# MCU_B.net
KiCad netlist of a schematic drawn in Altium Designer
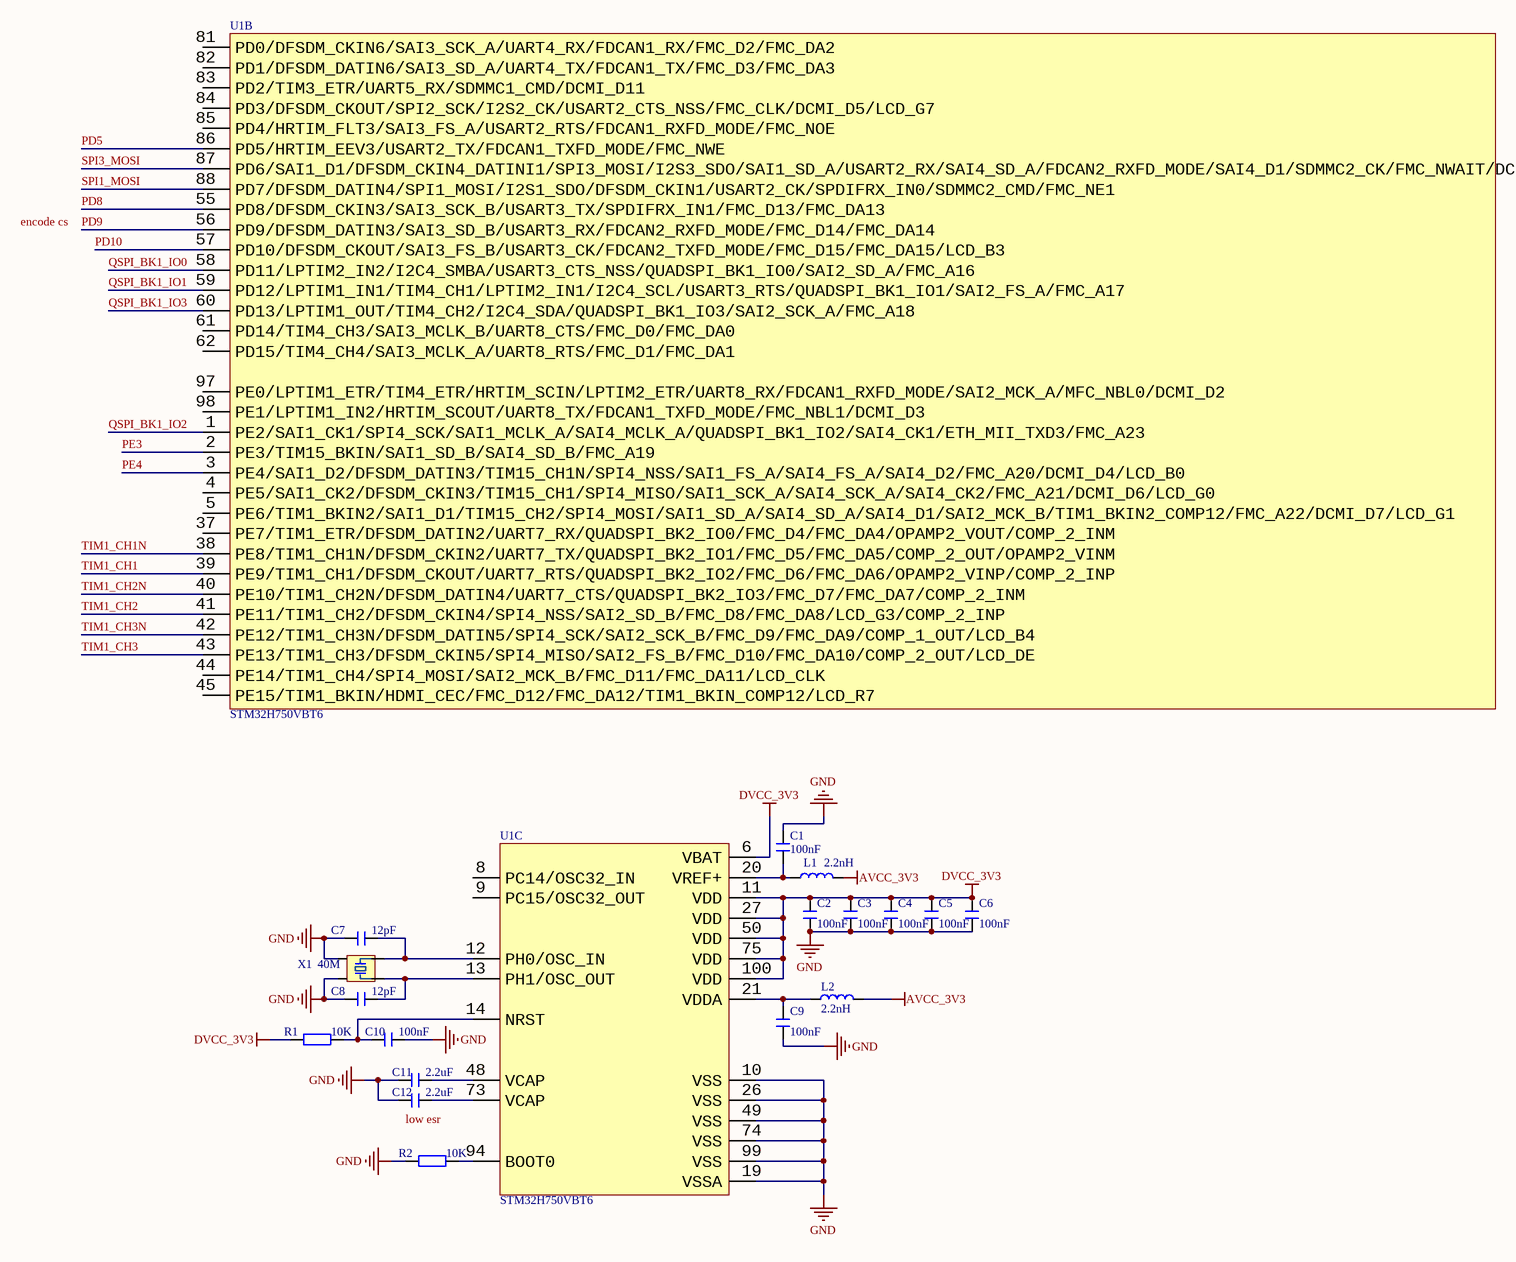
[diagram p0: MCU_B.SchDoc]

(export (version "E")
  (design (tool "Eeschema 10.0.6"))
  (components
    (comp (ref "C1")
      (value "100nF")
      (footprint "C 0402_L")
      (description "无极性贴片电容")
      (fields (field (name "版权归属") "源创客"))
      (libsource (lib "3.1   - 电阻-电容-电感") (part "C"))
    )
    (comp (ref "C2")
      (value "100nF")
      (footprint "C 0402_L")
      (description "无极性贴片电容")
      (fields (field (name "版权归属") "源创客"))
      (libsource (lib "3.1   - 电阻-电容-电感") (part "C"))
    )
    (comp (ref "C3")
      (value "100nF")
      (footprint "C 0402_L")
      (description "无极性贴片电容")
      (fields (field (name "版权归属") "源创客"))
      (libsource (lib "3.1   - 电阻-电容-电感") (part "C"))
    )
    (comp (ref "C4")
      (value "100nF")
      (footprint "C 0402_L")
      (description "无极性贴片电容")
      (fields (field (name "版权归属") "源创客"))
      (libsource (lib "3.1   - 电阻-电容-电感") (part "C"))
    )
    (comp (ref "C5")
      (value "100nF")
      (footprint "C 0402_L")
      (description "无极性贴片电容")
      (fields (field (name "版权归属") "源创客"))
      (libsource (lib "3.1   - 电阻-电容-电感") (part "C"))
    )
    (comp (ref "C6")
      (value "100nF")
      (footprint "C 0402_L")
      (description "无极性贴片电容")
      (fields (field (name "版权归属") "源创客"))
      (libsource (lib "3.1   - 电阻-电容-电感") (part "C"))
    )
    (comp (ref "C7")
      (value "12pF")
      (footprint "C 0402_L")
      (description "无极性贴片电容")
      (fields (field (name "版权归属") "源创客"))
      (libsource (lib "3.1   - 电阻-电容-电感") (part "C"))
    )
    (comp (ref "C8")
      (value "12pF")
      (footprint "C 0402_L")
      (description "无极性贴片电容")
      (fields (field (name "版权归属") "源创客"))
      (libsource (lib "3.1   - 电阻-电容-电感") (part "C"))
    )
    (comp (ref "C9")
      (value "100nF")
      (footprint "C 0402_L")
      (description "无极性贴片电容")
      (fields (field (name "版权归属") "源创客"))
      (libsource (lib "3.1   - 电阻-电容-电感") (part "C"))
    )
    (comp (ref "C10")
      (value "100nF")
      (footprint "C 0402_L")
      (description "无极性贴片电容")
      (fields (field (name "版权归属") "源创客"))
      (libsource (lib "3.1   - 电阻-电容-电感") (part "C"))
    )
    (comp (ref "C11")
      (value "2.2uF")
      (footprint "C 0402_L")
      (description "无极性贴片电容")
      (fields (field (name "版权归属") "源创客"))
      (libsource (lib "3.1   - 电阻-电容-电感") (part "C"))
    )
    (comp (ref "C12")
      (value "2.2uF")
      (footprint "C 0402_L")
      (description "无极性贴片电容")
      (fields (field (name "版权归属") "源创客"))
      (libsource (lib "3.1   - 电阻-电容-电感") (part "C"))
    )
    (comp (ref "L1")
      (value "2.2nH")
      (footprint "L 0402")
      (description "小功率贴片电感")
      (fields (field (name "版权归属") "源创客"))
      (libsource (lib "3.1   - 电阻-电容-电感") (part "L"))
    )
    (comp (ref "L2")
      (value "2.2nH")
      (footprint "L 0402")
      (description "小功率贴片电感")
      (fields (field (name "版权归属") "源创客"))
      (libsource (lib "3.1   - 电阻-电容-电感") (part "L"))
    )
    (comp (ref "R1")
      (value "10K")
      (footprint "R 0402_L")
      (description "贴片电阻")
      (fields (field (name "版权归属") "源创客"))
      (libsource (lib "3.1   - 电阻-电容-电感") (part "R"))
    )
    (comp (ref "R2")
      (value "10K")
      (footprint "R 0402_L")
      (description "贴片电阻")
      (fields (field (name "版权归属") "源创客"))
      (libsource (lib "3.1   - 电阻-电容-电感") (part "R"))
    )
    (comp (ref "U1")
      (value "STM32H750VBT6")
      (footprint "LQFP100 14x14_L")
      (libsource (lib "STM32芯片") (part "STM32H750VBT6"))
    )
    (comp (ref "X1")
      (value "40M")
      (footprint "OSC 2016-4P")
      (description "4脚无源晶振")
      (fields (field (name "版权归属") "源创客"))
      (libsource (lib "10.1 - 保险丝-晶振") (part "XTAL-4P"))
    )
  )
  (nets
    (net (code "1") (name "/PD5") (class "Default")
      (node (ref "U1") (pin "86") (pinfunction "PD5/HRTIM_EEV3/USART2_TX/FDCAN1_TXFD_MODE/FMC_NWE_86") (pintype "passive"))
    )
    (net (code "2") (name "/PD8") (class "Default")
      (node (ref "U1") (pin "55") (pinfunction "PD8/DFSDM_CKIN3/SAI3_SCK_B/USART3_TX/SPDIFRX_IN1/FMC_D13/FMC_DA13_55") (pintype "passive"))
    )
    (net (code "3") (name "/PD9") (class "Default")
      (node (ref "U1") (pin "56") (pinfunction "PD9/DFSDM_DATIN3/SAI3_SD_B/USART3_RX/FDCAN2_RXFD_MODE/FMC_D14/FMC_DA14_56") (pintype "passive"))
    )
    (net (code "4") (name "/PD10") (class "Default")
      (node (ref "U1") (pin "57") (pinfunction "PD10/DFSDM_CKOUT/SAI3_FS_B/USART3_CK/FDCAN2_TXFD_MODE/FMC_D15/FMC_DA15/LCD_B3_57") (pintype "passive"))
    )
    (net (code "5") (name "/PE3") (class "Default")
      (node (ref "U1") (pin "2") (pinfunction "PE3/TIM15_BKIN/SAI1_SD_B/SAI4_SD_B/FMC_A19_2") (pintype "passive"))
    )
    (net (code "6") (name "/PE4") (class "Default")
      (node (ref "U1") (pin "3") (pinfunction "PE4/SAI1_D2/DFSDM_DATIN3/TIM15_CH1N/SPI4_NSS/SAI1_FS_A/SAI4_FS_A/SAI4_D2/FMC_A20/DCMI_D4/LCD_B0_3") (pintype "passive"))
    )
    (net (code "7") (name "/QSPI_BK1_IO0") (class "Default")
      (node (ref "U1") (pin "58") (pinfunction "PD11/LPTIM2_IN2/I2C4_SMBA/USART3_CTS_NSS/QUADSPI_BK1_IO0/SAI2_SD_A/FMC_A16_58") (pintype "passive"))
    )
    (net (code "8") (name "/QSPI_BK1_IO1") (class "Default")
      (node (ref "U1") (pin "59") (pinfunction "PD12/LPTIM1_IN1/TIM4_CH1/LPTIM2_IN1/I2C4_SCL/USART3_RTS/QUADSPI_BK1_IO1/SAI2_FS_A/FMC_A17_59") (pintype "passive"))
    )
    (net (code "9") (name "/QSPI_BK1_IO2") (class "Default")
      (node (ref "U1") (pin "1") (pinfunction "PE2/SAI1_CK1/SPI4_SCK/SAI1_MCLK_A/SAI4_MCLK_A/QUADSPI_BK1_IO2/SAI4_CK1/ETH_MII_TXD3/FMC_A23_1") (pintype "passive"))
    )
    (net (code "10") (name "/QSPI_BK1_IO3") (class "Default")
      (node (ref "U1") (pin "60") (pinfunction "PD13/LPTIM1_OUT/TIM4_CH2/I2C4_SDA/QUADSPI_BK1_IO3/SAI2_SCK_A/FMC_A18_60") (pintype "passive"))
    )
    (net (code "11") (name "/SPI1_MOSI") (class "Default")
      (node (ref "U1") (pin "88") (pinfunction "PD7/DFSDM_DATIN4/SPI1_MOSI/I2S1_SDO/DFSDM_CKIN1/USART2_CK/SPDIFRX_IN0/SDMMC2_CMD/FMC_NE1_88") (pintype "passive"))
    )
    (net (code "12") (name "/SPI3_MOSI") (class "Default")
      (node (ref "U1") (pin "87") (pinfunction "PD6/SAI1_D1/DFSDM_CKIN4_DATINI1/SPI3_MOSI/I2S3_SDO/SAI1_SD_A/USART2_RX/SAI4_SD_A/FDCAN2_RXFD_MODE/SAI4_D1/SDMMC2_CK/FMC_NWAIT/DCMI_D10/LCD_B2_87") (pintype "passive"))
    )
    (net (code "13") (name "/TIM1_CH1") (class "Default")
      (node (ref "U1") (pin "39") (pinfunction "PE9/TIM1_CH1/DFSDM_CKOUT/UART7_RTS/QUADSPI_BK2_IO2/FMC_D6/FMC_DA6/OPAMP2_VINP/COMP_2_INP_39") (pintype "passive"))
    )
    (net (code "14") (name "/TIM1_CH1N") (class "Default")
      (node (ref "U1") (pin "38") (pinfunction "PE8/TIM1_CH1N/DFSDM_CKIN2/UART7_TX/QUADSPI_BK2_IO1/FMC_D5/FMC_DA5/COMP_2_OUT/OPAMP2_VINM_38") (pintype "passive"))
    )
    (net (code "15") (name "/TIM1_CH2") (class "Default")
      (node (ref "U1") (pin "41") (pinfunction "PE11/TIM1_CH2/DFSDM_CKIN4/SPI4_NSS/SAI2_SD_B/FMC_D8/FMC_DA8/LCD_G3/COMP_2_INP_41") (pintype "passive"))
    )
    (net (code "16") (name "/TIM1_CH2N") (class "Default")
      (node (ref "U1") (pin "40") (pinfunction "PE10/TIM1_CH2N/DFSDM_DATIN4/UART7_CTS/QUADSPI_BK2_IO3/FMC_D7/FMC_DA7/COMP_2_INM_40") (pintype "passive"))
    )
    (net (code "17") (name "/TIM1_CH3") (class "Default")
      (node (ref "U1") (pin "43") (pinfunction "PE13/TIM1_CH3/DFSDM_CKIN5/SPI4_MISO/SAI2_FS_B/FMC_D10/FMC_DA10/COMP_2_OUT/LCD_DE_43") (pintype "passive"))
    )
    (net (code "18") (name "/TIM1_CH3N") (class "Default")
      (node (ref "U1") (pin "42") (pinfunction "PE12/TIM1_CH3N/DFSDM_DATIN5/SPI4_SCK/SAI2_SCK_B/FMC_D9/FMC_DA9/COMP_1_OUT/LCD_B4_42") (pintype "passive"))
    )
    (net (code "19") (name "AVCC_3V3") (class "Default")
      (node (ref "L1") (pin "2") (pinfunction "2_2") (pintype "passive"))
      (node (ref "L2") (pin "2") (pinfunction "2_2") (pintype "passive"))
    )
    (net (code "20") (name "DVCC_3V3") (class "Default")
      (node (ref "C2") (pin "2") (pinfunction "2_2") (pintype "passive"))
      (node (ref "C3") (pin "2") (pinfunction "2_2") (pintype "passive"))
      (node (ref "C4") (pin "2") (pinfunction "2_2") (pintype "passive"))
      (node (ref "C5") (pin "2") (pinfunction "2_2") (pintype "passive"))
      (node (ref "C6") (pin "2") (pinfunction "2_2") (pintype "passive"))
      (node (ref "R1") (pin "1") (pinfunction "1_1") (pintype "passive"))
      (node (ref "U1") (pin "100") (pinfunction "VDD_100") (pintype "passive"))
      (node (ref "U1") (pin "11") (pinfunction "VDD_11") (pintype "passive"))
      (node (ref "U1") (pin "27") (pinfunction "VDD_27") (pintype "passive"))
      (node (ref "U1") (pin "50") (pinfunction "VDD_50") (pintype "passive"))
      (node (ref "U1") (pin "6") (pinfunction "VBAT_6") (pintype "passive"))
      (node (ref "U1") (pin "75") (pinfunction "VDD_75") (pintype "passive"))
    )
    (net (code "21") (name "GND") (class "Default")
      (node (ref "C1") (pin "2") (pinfunction "2_2") (pintype "passive"))
      (node (ref "C10") (pin "2") (pinfunction "2_2") (pintype "passive"))
      (node (ref "C11") (pin "1") (pinfunction "1_1") (pintype "passive"))
      (node (ref "C12") (pin "1") (pinfunction "1_1") (pintype "passive"))
      (node (ref "C2") (pin "1") (pinfunction "1_1") (pintype "passive"))
      (node (ref "C3") (pin "1") (pinfunction "1_1") (pintype "passive"))
      (node (ref "C4") (pin "1") (pinfunction "1_1") (pintype "passive"))
      (node (ref "C5") (pin "1") (pinfunction "1_1") (pintype "passive"))
      (node (ref "C6") (pin "1") (pinfunction "1_1") (pintype "passive"))
      (node (ref "C7") (pin "1") (pinfunction "1_1") (pintype "passive"))
      (node (ref "C8") (pin "1") (pinfunction "1_1") (pintype "passive"))
      (node (ref "C9") (pin "1") (pinfunction "1_1") (pintype "passive"))
      (node (ref "R2") (pin "1") (pinfunction "1_1") (pintype "passive"))
      (node (ref "U1") (pin "10") (pinfunction "VSS_10") (pintype "passive"))
      (node (ref "U1") (pin "19") (pinfunction "VSSA_19") (pintype "passive"))
      (node (ref "U1") (pin "26") (pinfunction "VSS_26") (pintype "passive"))
      (node (ref "U1") (pin "49") (pinfunction "VSS_49") (pintype "passive"))
      (node (ref "U1") (pin "74") (pinfunction "VSS_74") (pintype "passive"))
      (node (ref "U1") (pin "99") (pinfunction "VSS_99") (pintype "passive"))
      (node (ref "X1") (pin "2") (pinfunction "2_2") (pintype "passive"))
      (node (ref "X1") (pin "4") (pinfunction "4_4") (pintype "passive"))
    )
    (net (code "22") (name "Net-(C11-Pad2)") (class "Default")
      (node (ref "C11") (pin "2") (pinfunction "2_2") (pintype "passive"))
      (node (ref "U1") (pin "48") (pinfunction "VCAP_48") (pintype "passive"))
    )
    (net (code "23") (name "Net-(C12-Pad2)") (class "Default")
      (node (ref "C12") (pin "2") (pinfunction "2_2") (pintype "passive"))
      (node (ref "U1") (pin "73") (pinfunction "VCAP_73") (pintype "passive"))
    )
    (net (code "24") (name "Net-(U1C-BOOT0)") (class "Default")
      (node (ref "R2") (pin "2") (pinfunction "2_2") (pintype "passive"))
      (node (ref "U1") (pin "94") (pinfunction "BOOT0_94") (pintype "passive"))
    )
    (net (code "25") (name "Net-(U1C-NRST)") (class "Default")
      (node (ref "C10") (pin "1") (pinfunction "1_1") (pintype "passive"))
      (node (ref "R1") (pin "2") (pinfunction "2_2") (pintype "passive"))
      (node (ref "U1") (pin "14") (pinfunction "NRST_14") (pintype "passive"))
    )
    (net (code "26") (name "Net-(U1C-PH0{slash}OSC_IN)") (class "Default")
      (node (ref "C7") (pin "2") (pinfunction "2_2") (pintype "passive"))
      (node (ref "U1") (pin "12") (pinfunction "PH0/OSC_IN_12") (pintype "passive"))
      (node (ref "X1") (pin "1") (pinfunction "1_1") (pintype "passive"))
    )
    (net (code "27") (name "Net-(U1C-PH1{slash}OSC_OUT)") (class "Default")
      (node (ref "C8") (pin "2") (pinfunction "2_2") (pintype "passive"))
      (node (ref "U1") (pin "13") (pinfunction "PH1/OSC_OUT_13") (pintype "passive"))
      (node (ref "X1") (pin "3") (pinfunction "3_3") (pintype "passive"))
    )
    (net (code "28") (name "Net-(U1C-VDDA)") (class "Default")
      (node (ref "C9") (pin "2") (pinfunction "2_2") (pintype "passive"))
      (node (ref "L2") (pin "1") (pinfunction "1_1") (pintype "passive"))
      (node (ref "U1") (pin "21") (pinfunction "VDDA_21") (pintype "passive"))
    )
    (net (code "29") (name "Net-(U1C-VREF+)") (class "Default")
      (node (ref "C1") (pin "1") (pinfunction "1_1") (pintype "passive"))
      (node (ref "L1") (pin "1") (pinfunction "1_1") (pintype "passive"))
      (node (ref "U1") (pin "20") (pinfunction "VREF+_20") (pintype "passive"))
    )
    (net (code "30") (name "unconnected-(U1B-PD0{slash}DFSDM_CKIN6{slash}SAI3_SCK_A{slash}UART4_RX{slash}FDCAN1_RX{slash}FMC_D2{slash}FMC_DA2-Pad81)") (class "Default")
      (node (ref "U1") (pin "81") (pinfunction "PD0/DFSDM_CKIN6/SAI3_SCK_A/UART4_RX/FDCAN1_RX/FMC_D2/FMC_DA2_81") (pintype "passive"))
    )
    (net (code "31") (name "unconnected-(U1B-PD1{slash}DFSDM_DATIN6{slash}SAI3_SD_A{slash}UART4_TX{slash}FDCAN1_TX{slash}FMC_D3{slash}FMC_DA3-Pad82)") (class "Default")
      (node (ref "U1") (pin "82") (pinfunction "PD1/DFSDM_DATIN6/SAI3_SD_A/UART4_TX/FDCAN1_TX/FMC_D3/FMC_DA3_82") (pintype "passive"))
    )
    (net (code "32") (name "unconnected-(U1B-PD2{slash}TIM3_ETR{slash}UART5_RX{slash}SDMMC1_CMD{slash}DCMI_D11-Pad83)") (class "Default")
      (node (ref "U1") (pin "83") (pinfunction "PD2/TIM3_ETR/UART5_RX/SDMMC1_CMD/DCMI_D11_83") (pintype "passive"))
    )
    (net (code "33") (name "unconnected-(U1B-PD3{slash}DFSDM_CKOUT{slash}SPI2_SCK{slash}I2S2_CK{slash}USART2_CTS_NSS{slash}FMC_CLK{slash}DCMI_D5{slash}LCD_G7-Pad84)") (class "Default")
      (node (ref "U1") (pin "84") (pinfunction "PD3/DFSDM_CKOUT/SPI2_SCK/I2S2_CK/USART2_CTS_NSS/FMC_CLK/DCMI_D5/LCD_G7_84") (pintype "passive"))
    )
    (net (code "34") (name "unconnected-(U1B-PD4{slash}HRTIM_FLT3{slash}SAI3_FS_A{slash}USART2_RTS{slash}FDCAN1_RXFD_MODE{slash}FMC_NOE-Pad85)") (class "Default")
      (node (ref "U1") (pin "85") (pinfunction "PD4/HRTIM_FLT3/SAI3_FS_A/USART2_RTS/FDCAN1_RXFD_MODE/FMC_NOE_85") (pintype "passive"))
    )
    (net (code "35") (name "unconnected-(U1B-PD14{slash}TIM4_CH3{slash}SAI3_MCLK_B{slash}UART8_CTS{slash}FMC_D0{slash}FMC_DA0-Pad61)") (class "Default")
      (node (ref "U1") (pin "61") (pinfunction "PD14/TIM4_CH3/SAI3_MCLK_B/UART8_CTS/FMC_D0/FMC_DA0_61") (pintype "passive"))
    )
    (net (code "36") (name "unconnected-(U1B-PD15{slash}TIM4_CH4{slash}SAI3_MCLK_A{slash}UART8_RTS{slash}FMC_D1{slash}FMC_DA1-Pad62)") (class "Default")
      (node (ref "U1") (pin "62") (pinfunction "PD15/TIM4_CH4/SAI3_MCLK_A/UART8_RTS/FMC_D1/FMC_DA1_62") (pintype "passive"))
    )
    (net (code "37") (name "unconnected-(U1B-PE0{slash}LPTIM1_ETR{slash}TIM4_ETR{slash}HRTIM_SCIN{slash}LPTIM2_ETR{slash}UART8_RX{slash}FDCAN1_RXFD_MODE{slash}SAI2_MCK_A{slash}MFC_NBL0{slash}DCMI_D2-Pad97)") (class "Default")
      (node (ref "U1") (pin "97") (pinfunction "PE0/LPTIM1_ETR/TIM4_ETR/HRTIM_SCIN/LPTIM2_ETR/UART8_RX/FDCAN1_RXFD_MODE/SAI2_MCK_A/MFC_NBL0/DCMI_D2_97") (pintype "passive"))
    )
    (net (code "38") (name "unconnected-(U1B-PE1{slash}LPTIM1_IN2{slash}HRTIM_SCOUT{slash}UART8_TX{slash}FDCAN1_TXFD_MODE{slash}FMC_NBL1{slash}DCMI_D3-Pad98)") (class "Default")
      (node (ref "U1") (pin "98") (pinfunction "PE1/LPTIM1_IN2/HRTIM_SCOUT/UART8_TX/FDCAN1_TXFD_MODE/FMC_NBL1/DCMI_D3_98") (pintype "passive"))
    )
    (net (code "39") (name "unconnected-(U1B-PE5{slash}SAI1_CK2{slash}DFSDM_CKIN3{slash}TIM15_CH1{slash}SPI4_MISO{slash}SAI1_SCK_A{slash}SAI4_SCK_A{slash}SAI4_CK2{slash}FMC_A21{slash}DCMI_D6{slash}LCD_G0-Pad4)") (class "Default")
      (node (ref "U1") (pin "4") (pinfunction "PE5/SAI1_CK2/DFSDM_CKIN3/TIM15_CH1/SPI4_MISO/SAI1_SCK_A/SAI4_SCK_A/SAI4_CK2/FMC_A21/DCMI_D6/LCD_G0_4") (pintype "passive"))
    )
    (net (code "40") (name "unconnected-(U1B-PE6{slash}TIM1_BKIN2{slash}SAI1_D1{slash}TIM15_CH2{slash}SPI4_MOSI{slash}SAI1_SD_A{slash}SAI4_SD_A{slash}SAI4_D1{slash}SAI2_MCK_B{slash}TIM1_BKIN2_COMP12{slash}FMC_A22{slash}DCMI_D7{slash}LCD_G1-Pad5)") (class "Default")
      (node (ref "U1") (pin "5") (pinfunction "PE6/TIM1_BKIN2/SAI1_D1/TIM15_CH2/SPI4_MOSI/SAI1_SD_A/SAI4_SD_A/SAI4_D1/SAI2_MCK_B/TIM1_BKIN2_COMP12/FMC_A22/DCMI_D7/LCD_G1_5") (pintype "passive"))
    )
    (net (code "41") (name "unconnected-(U1B-PE7{slash}TIM1_ETR{slash}DFSDM_DATIN2{slash}UART7_RX{slash}QUADSPI_BK2_IO0{slash}FMC_D4{slash}FMC_DA4{slash}OPAMP2_VOUT{slash}COMP_2_INM-Pad37)") (class "Default")
      (node (ref "U1") (pin "37") (pinfunction "PE7/TIM1_ETR/DFSDM_DATIN2/UART7_RX/QUADSPI_BK2_IO0/FMC_D4/FMC_DA4/OPAMP2_VOUT/COMP_2_INM_37") (pintype "passive"))
    )
    (net (code "42") (name "unconnected-(U1B-PE14{slash}TIM1_CH4{slash}SPI4_MOSI{slash}SAI2_MCK_B{slash}FMC_D11{slash}FMC_DA11{slash}LCD_CLK-Pad44)") (class "Default")
      (node (ref "U1") (pin "44") (pinfunction "PE14/TIM1_CH4/SPI4_MOSI/SAI2_MCK_B/FMC_D11/FMC_DA11/LCD_CLK_44") (pintype "passive"))
    )
    (net (code "43") (name "unconnected-(U1B-PE15{slash}TIM1_BKIN{slash}HDMI_CEC{slash}FMC_D12{slash}FMC_DA12{slash}TIM1_BKIN_COMP12{slash}LCD_R7-Pad45)") (class "Default")
      (node (ref "U1") (pin "45") (pinfunction "PE15/TIM1_BKIN/HDMI_CEC/FMC_D12/FMC_DA12/TIM1_BKIN_COMP12/LCD_R7_45") (pintype "passive"))
    )
    (net (code "44") (name "unconnected-(U1C-PC14{slash}OSC32_IN-Pad8)") (class "Default")
      (node (ref "U1") (pin "8") (pinfunction "PC14/OSC32_IN_8") (pintype "passive"))
    )
    (net (code "45") (name "unconnected-(U1C-PC15{slash}OSC32_OUT-Pad9)") (class "Default")
      (node (ref "U1") (pin "9") (pinfunction "PC15/OSC32_OUT_9") (pintype "passive"))
    )
  )
)
